# StereoOutputBoard.net
KiCad netlist of a schematic drawn in EAGLE
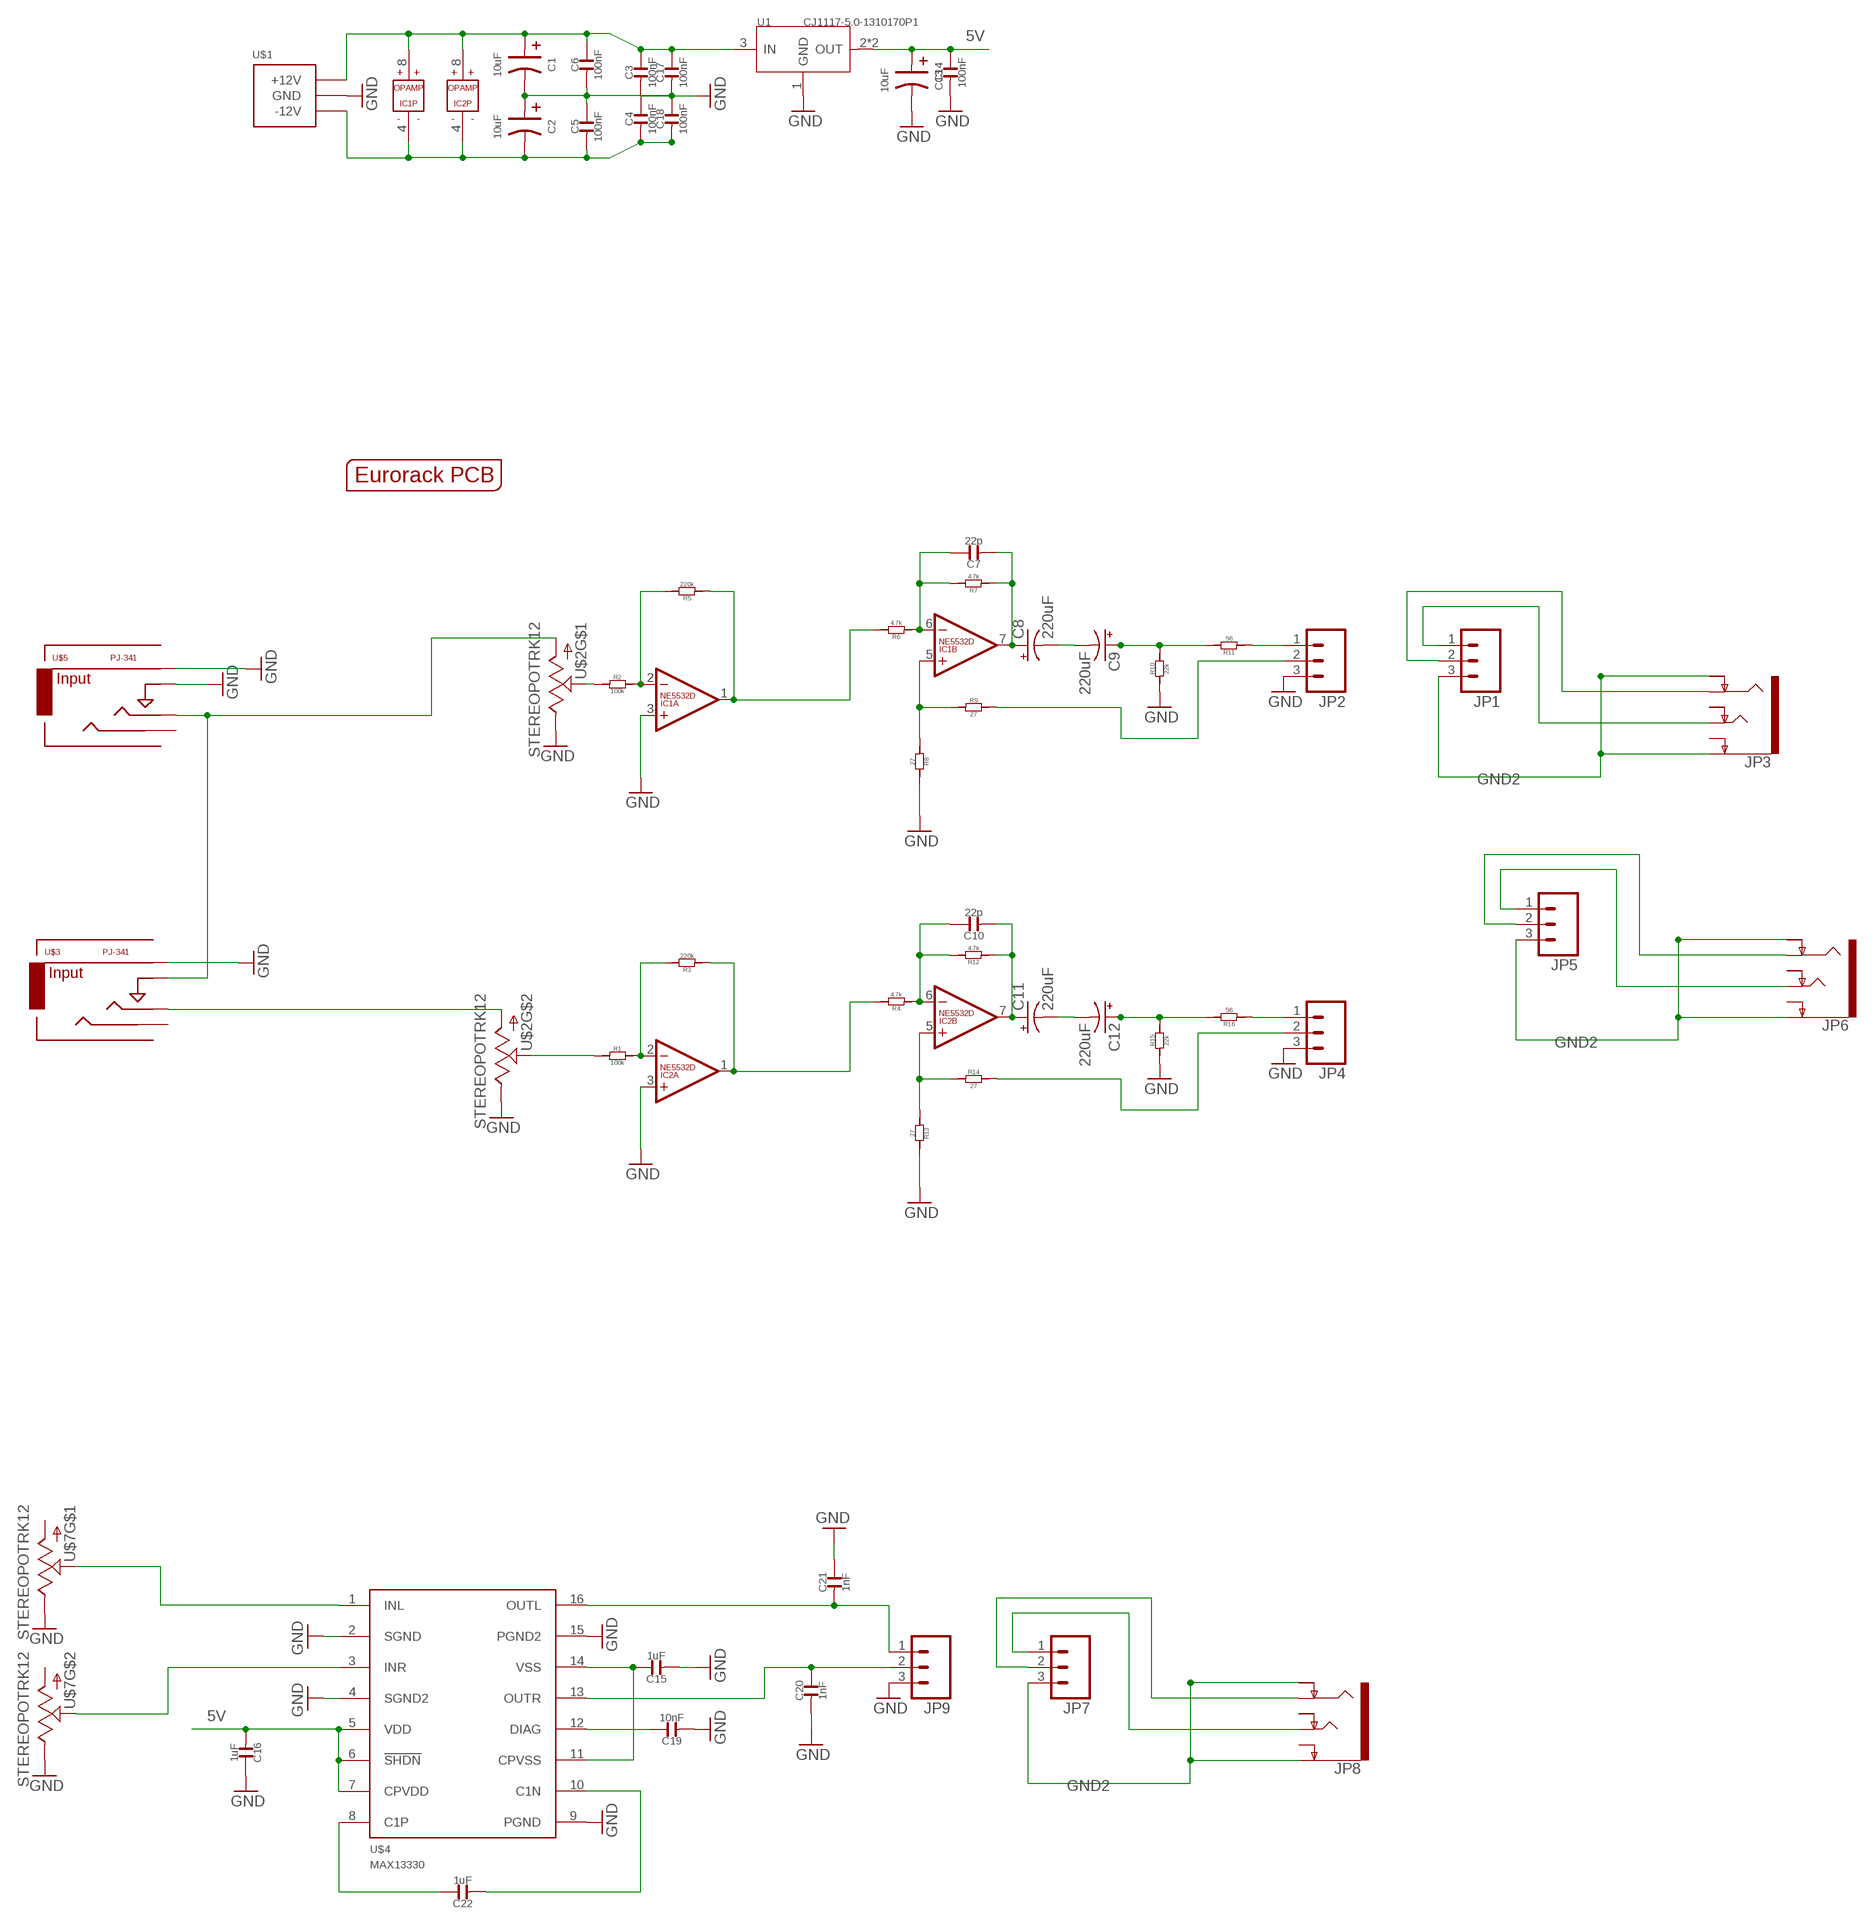
[diagram p0: schematic, sheet 1]

(export (version "E")
  (design (tool "Eeschema 10.0.6"))
  (components
    (comp (ref "C1")
      (value "10uF")
      (footprint "eagle-import:AVX-A")
      (libsource (lib "eagle-import") (part "C-POLAR-A"))
    )
    (comp (ref "C2")
      (value "10uF")
      (footprint "eagle-import:AVX-A")
      (libsource (lib "eagle-import") (part "C-POLAR-A"))
    )
    (comp (ref "C3")
      (value "100nF")
      (footprint "eagle-import:C0603")
      (libsource (lib "eagle-import") (part "C-0603"))
    )
    (comp (ref "C4")
      (value "100nF")
      (footprint "eagle-import:C0603")
      (libsource (lib "eagle-import") (part "C-0603"))
    )
    (comp (ref "C5")
      (value "100nF")
      (footprint "eagle-import:C0603")
      (libsource (lib "eagle-import") (part "C-0603"))
    )
    (comp (ref "C6")
      (value "100nF")
      (footprint "eagle-import:C0603")
      (libsource (lib "eagle-import") (part "C-0603"))
    )
    (comp (ref "C7")
      (value "22p")
      (footprint "eagle-import:C0603")
      (libsource (lib "eagle-import") (part "C-0603"))
    )
    (comp (ref "C8")
      (value "220uF")
      (footprint "eagle-import:153CLV-0505")
      (libsource (lib "eagle-import") (part "CPOL-US153CLV-0505"))
    )
    (comp (ref "C9")
      (value "220uF")
      (footprint "eagle-import:153CLV-0505")
      (libsource (lib "eagle-import") (part "CPOL-US153CLV-0505"))
    )
    (comp (ref "C10")
      (value "22p")
      (footprint "eagle-import:C0603")
      (libsource (lib "eagle-import") (part "C-0603"))
    )
    (comp (ref "C11")
      (value "220uF")
      (footprint "eagle-import:153CLV-0505")
      (libsource (lib "eagle-import") (part "CPOL-US153CLV-0505"))
    )
    (comp (ref "C12")
      (value "220uF")
      (footprint "eagle-import:153CLV-0505")
      (libsource (lib "eagle-import") (part "CPOL-US153CLV-0505"))
    )
    (comp (ref "C13")
      (value "10uF")
      (footprint "eagle-import:AVX-A")
      (libsource (lib "eagle-import") (part "C-POLAR-A"))
    )
    (comp (ref "C14")
      (value "100nF")
      (footprint "eagle-import:C0603")
      (libsource (lib "eagle-import") (part "C-0603"))
    )
    (comp (ref "C15")
      (value "1uF")
      (footprint "eagle-import:C0603")
      (libsource (lib "eagle-import") (part "C-0603"))
    )
    (comp (ref "C16")
      (value "1uF")
      (footprint "eagle-import:C0603")
      (libsource (lib "eagle-import") (part "C-0603"))
    )
    (comp (ref "C17")
      (value "100nF")
      (footprint "eagle-import:C0603")
      (libsource (lib "eagle-import") (part "C-0603"))
    )
    (comp (ref "C18")
      (value "100nF")
      (footprint "eagle-import:C0603")
      (libsource (lib "eagle-import") (part "C-0603"))
    )
    (comp (ref "C19")
      (value "10nF")
      (footprint "eagle-import:C0603")
      (libsource (lib "eagle-import") (part "C-0603"))
    )
    (comp (ref "C20")
      (value "1nF")
      (footprint "eagle-import:C0603")
      (libsource (lib "eagle-import") (part "C-0603"))
    )
    (comp (ref "C21")
      (value "1nF")
      (footprint "eagle-import:C0603")
      (libsource (lib "eagle-import") (part "C-0603"))
    )
    (comp (ref "C22")
      (value "1uF")
      (footprint "eagle-import:C0603")
      (libsource (lib "eagle-import") (part "C-0603"))
    )
    (comp (ref "IC1")
      (value "NE5532D")
      (footprint "eagle-import:SO08")
      (libsource (lib "eagle-import") (part "NE5532D"))
    )
    (comp (ref "IC2")
      (value "NE5532D")
      (footprint "eagle-import:SO08")
      (libsource (lib "eagle-import") (part "NE5532D"))
    )
    (comp (ref "JP1")
      (value "M03PTH")
      (footprint "eagle-import:1X03")
      (libsource (lib "eagle-import") (part "M03PTH"))
    )
    (comp (ref "JP2")
      (value "M03PTH")
      (footprint "eagle-import:1X03")
      (libsource (lib "eagle-import") (part "M03PTH"))
    )
    (comp (ref "JP3")
      (value "AUDIO-JACK4-.25-HORIZ-TRS")
      (footprint "eagle-import:AUDIO-JACK-.25-INCH-HORIZ-PTH")
      (libsource (lib "eagle-import") (part "AUDIO-JACK4-.25-HORIZ-TRS"))
    )
    (comp (ref "JP4")
      (value "M03PTH")
      (footprint "eagle-import:1X03")
      (libsource (lib "eagle-import") (part "M03PTH"))
    )
    (comp (ref "JP5")
      (value "M03PTH")
      (footprint "eagle-import:1X03")
      (libsource (lib "eagle-import") (part "M03PTH"))
    )
    (comp (ref "JP6")
      (value "AUDIO-JACK4-.25-HORIZ-TRS")
      (footprint "eagle-import:AUDIO-JACK-.25-INCH-HORIZ-PTH")
      (libsource (lib "eagle-import") (part "AUDIO-JACK4-.25-HORIZ-TRS"))
    )
    (comp (ref "JP7")
      (value "M03PTH")
      (footprint "eagle-import:1X03")
      (libsource (lib "eagle-import") (part "M03PTH"))
    )
    (comp (ref "JP8")
      (value "AUDIO-JACK4-.25-HORIZ-TRS")
      (footprint "eagle-import:AUDIO-JACK-.25-INCH-HORIZ-PTH")
      (libsource (lib "eagle-import") (part "AUDIO-JACK4-.25-HORIZ-TRS"))
    )
    (comp (ref "JP9")
      (value "M03PTH")
      (footprint "eagle-import:1X03")
      (libsource (lib "eagle-import") (part "M03PTH"))
    )
    (comp (ref "R1")
      (value "100k")
      (footprint "eagle-import:R0603")
      (libsource (lib "eagle-import") (part "R-0603"))
    )
    (comp (ref "R2")
      (value "100k")
      (footprint "eagle-import:R0603")
      (libsource (lib "eagle-import") (part "R-0603"))
    )
    (comp (ref "R3")
      (value "220k")
      (footprint "eagle-import:R0603")
      (libsource (lib "eagle-import") (part "R-0603"))
    )
    (comp (ref "R4")
      (value "4.7k")
      (footprint "eagle-import:R0603")
      (libsource (lib "eagle-import") (part "R-0603"))
    )
    (comp (ref "R5")
      (value "220k")
      (footprint "eagle-import:R0603")
      (libsource (lib "eagle-import") (part "R-0603"))
    )
    (comp (ref "R6")
      (value "4.7k")
      (footprint "eagle-import:R0603")
      (libsource (lib "eagle-import") (part "R-0603"))
    )
    (comp (ref "R7")
      (value "4.7k")
      (footprint "eagle-import:R0603")
      (libsource (lib "eagle-import") (part "R-0603"))
    )
    (comp (ref "R8")
      (value "27")
      (footprint "eagle-import:R0603")
      (libsource (lib "eagle-import") (part "R-0603"))
    )
    (comp (ref "R9")
      (value "27")
      (footprint "eagle-import:R0603")
      (libsource (lib "eagle-import") (part "R-0603"))
    )
    (comp (ref "R10")
      (value "22k")
      (footprint "eagle-import:R0603")
      (libsource (lib "eagle-import") (part "R-0603"))
    )
    (comp (ref "R11")
      (value "56")
      (footprint "eagle-import:R0603")
      (libsource (lib "eagle-import") (part "R-0603"))
    )
    (comp (ref "R12")
      (value "4.7k")
      (footprint "eagle-import:R0603")
      (libsource (lib "eagle-import") (part "R-0603"))
    )
    (comp (ref "R13")
      (value "27")
      (footprint "eagle-import:R0603")
      (libsource (lib "eagle-import") (part "R-0603"))
    )
    (comp (ref "R14")
      (value "27")
      (footprint "eagle-import:R0603")
      (libsource (lib "eagle-import") (part "R-0603"))
    )
    (comp (ref "R15")
      (value "22k")
      (footprint "eagle-import:R0603")
      (libsource (lib "eagle-import") (part "R-0603"))
    )
    (comp (ref "R16")
      (value "56")
      (footprint "eagle-import:R0603")
      (libsource (lib "eagle-import") (part "R-0603"))
    )
    (comp (ref "U$1")
      (value "POWER_SIMPLE")
      (footprint "eagle-import:2X05_SMT_HEADER")
      (libsource (lib "eagle-import") (part "POWER_SIMPLE"))
    )
    (comp (ref "U$2")
      (value "STEREOPOTRK12")
      (footprint "eagle-import:RK12")
      (libsource (lib "eagle-import") (part "STEREOPOTRK12"))
    )
    (comp (ref "U$3")
      (value "PJ-341")
      (footprint "eagle-import:3.5MM-JACK-SWITCH-13MM-INPUT")
      (libsource (lib "eagle-import") (part "AUDIO-JACKINPUT"))
    )
    (comp (ref "U$4")
      (value "MAX13330")
      (footprint "eagle-import:QSOP16")
      (libsource (lib "eagle-import") (part "MAX13330"))
    )
    (comp (ref "U$5")
      (value "PJ-341")
      (footprint "eagle-import:3.5MM-JACK-SWITCH-13MM-INPUT")
      (libsource (lib "eagle-import") (part "AUDIO-JACKINPUT"))
    )
    (comp (ref "U$6")
      (value "EURORACK_PCB4HP")
      (footprint "eagle-import:EURORACK4HPPCB")
      (libsource (lib "eagle-import") (part "EURORACK_PCB4HP"))
    )
    (comp (ref "U$7")
      (value "STEREOPOTRK12")
      (footprint "eagle-import:RK12")
      (libsource (lib "eagle-import") (part "STEREOPOTRK12"))
    )
    (comp (ref "U1")
      (value "CJ1117-5.0-1310170P1")
      (footprint "eagle-import:SOT223")
      (libsource (lib "eagle-import") (part "CJ1117-5.0-1310170P1"))
    )
  )
  (nets
    (net (code "1") (name "/5V") (class "Default")
      (node (ref "C13") (pin "+") (pinfunction "1_+") (pintype "bidirectional"))
      (node (ref "C14") (pin "2") (pinfunction "2_2") (pintype "bidirectional"))
      (node (ref "C16") (pin "1") (pinfunction "1_1") (pintype "bidirectional"))
      (node (ref "U$4") (pin "5") (pinfunction "VDD_5") (pintype "bidirectional"))
      (node (ref "U$4") (pin "6") (pinfunction "~{SHDN}_6") (pintype "bidirectional"))
      (node (ref "U$4") (pin "7") (pinfunction "CPVDD_7") (pintype "bidirectional"))
      (node (ref "U1") (pin "2") (pinfunction "OUT_2") (pintype "bidirectional"))
      (node (ref "U1") (pin "TER") (pinfunction "OUT_TER") (pintype "bidirectional"))
    )
    (net (code "2") (name "/GND2") (class "Default")
      (node (ref "JP1") (pin "3") (pinfunction "3_3") (pintype "passive"))
      (node (ref "JP3") (pin "P$2") (pinfunction "EARTH_P$2") (pintype "bidirectional"))
      (node (ref "JP3") (pin "P$5") (pinfunction "RING-NORM_P$5") (pintype "bidirectional"))
      (node (ref "JP5") (pin "3") (pinfunction "3_3") (pintype "passive"))
      (node (ref "JP6") (pin "P$2") (pinfunction "EARTH_P$2") (pintype "bidirectional"))
      (node (ref "JP6") (pin "P$5") (pinfunction "RING-NORM_P$5") (pintype "bidirectional"))
      (node (ref "JP7") (pin "3") (pinfunction "3_3") (pintype "passive"))
      (node (ref "JP8") (pin "P$2") (pinfunction "EARTH_P$2") (pintype "bidirectional"))
      (node (ref "JP8") (pin "P$5") (pinfunction "RING-NORM_P$5") (pintype "bidirectional"))
    )
    (net (code "3") (name "GND") (class "Default")
      (node (ref "C1") (pin "-") (pinfunction "2_-") (pintype "bidirectional"))
      (node (ref "C13") (pin "-") (pinfunction "2_-") (pintype "bidirectional"))
      (node (ref "C14") (pin "1") (pinfunction "1_1") (pintype "bidirectional"))
      (node (ref "C15") (pin "1") (pinfunction "1_1") (pintype "bidirectional"))
      (node (ref "C16") (pin "2") (pinfunction "2_2") (pintype "bidirectional"))
      (node (ref "C17") (pin "1") (pinfunction "1_1") (pintype "bidirectional"))
      (node (ref "C18") (pin "2") (pinfunction "2_2") (pintype "bidirectional"))
      (node (ref "C19") (pin "1") (pinfunction "1_1") (pintype "bidirectional"))
      (node (ref "C2") (pin "+") (pinfunction "1_+") (pintype "bidirectional"))
      (node (ref "C20") (pin "1") (pinfunction "1_1") (pintype "bidirectional"))
      (node (ref "C21") (pin "2") (pinfunction "2_2") (pintype "bidirectional"))
      (node (ref "C3") (pin "1") (pinfunction "1_1") (pintype "bidirectional"))
      (node (ref "C4") (pin "2") (pinfunction "2_2") (pintype "bidirectional"))
      (node (ref "C5") (pin "2") (pinfunction "2_2") (pintype "bidirectional"))
      (node (ref "C6") (pin "1") (pinfunction "1_1") (pintype "bidirectional"))
      (node (ref "IC1") (pin "3") (pinfunction "+IN_3") (pintype "input"))
      (node (ref "IC2") (pin "3") (pinfunction "+IN_3") (pintype "input"))
      (node (ref "JP2") (pin "3") (pinfunction "3_3") (pintype "passive"))
      (node (ref "JP4") (pin "3") (pinfunction "3_3") (pintype "passive"))
      (node (ref "JP9") (pin "3") (pinfunction "3_3") (pintype "passive"))
      (node (ref "R10") (pin "1") (pinfunction "1_1") (pintype "bidirectional"))
      (node (ref "R13") (pin "2") (pinfunction "2_2") (pintype "bidirectional"))
      (node (ref "R15") (pin "1") (pinfunction "1_1") (pintype "bidirectional"))
      (node (ref "R8") (pin "2") (pinfunction "2_2") (pintype "bidirectional"))
      (node (ref "U$1") (pin "3") (pinfunction "GND_3") (pintype "bidirectional"))
      (node (ref "U$1") (pin "4") (pinfunction "GND_4") (pintype "bidirectional"))
      (node (ref "U$1") (pin "5") (pinfunction "GND_5") (pintype "bidirectional"))
      (node (ref "U$1") (pin "6") (pinfunction "GND_6") (pintype "bidirectional"))
      (node (ref "U$1") (pin "7") (pinfunction "GND_7") (pintype "bidirectional"))
      (node (ref "U$1") (pin "8") (pinfunction "GND_8") (pintype "bidirectional"))
      (node (ref "U$2") (pin "R1_1") (pinfunction "E_R1_1") (pintype "passive"))
      (node (ref "U$2") (pin "R2_1") (pinfunction "E_R2_1") (pintype "passive"))
      (node (ref "U$3") (pin "RING@3") (pinfunction "RING_RING@3") (pintype "bidirectional"))
      (node (ref "U$4") (pin "15") (pinfunction "PGND2_15") (pintype "bidirectional"))
      (node (ref "U$4") (pin "2") (pinfunction "SGND_2") (pintype "bidirectional"))
      (node (ref "U$4") (pin "4") (pinfunction "SGND2_4") (pintype "bidirectional"))
      (node (ref "U$4") (pin "9") (pinfunction "PGND_9") (pintype "bidirectional"))
      (node (ref "U$5") (pin "RING@3") (pinfunction "RING_RING@3") (pintype "bidirectional"))
      (node (ref "U$5") (pin "SWITCH@3") (pinfunction "SWITCH_SWITCH@3") (pintype "bidirectional"))
      (node (ref "U$7") (pin "R1_1") (pinfunction "E_R1_1") (pintype "passive"))
      (node (ref "U$7") (pin "R2_1") (pinfunction "E_R2_1") (pintype "passive"))
      (node (ref "U1") (pin "1") (pinfunction "GND_1") (pintype "bidirectional"))
    )
    (net (code "4") (name "Net-(C1-1)") (class "Default")
      (node (ref "C1") (pin "+") (pinfunction "1_+") (pintype "bidirectional"))
      (node (ref "C17") (pin "2") (pinfunction "2_2") (pintype "bidirectional"))
      (node (ref "C3") (pin "2") (pinfunction "2_2") (pintype "bidirectional"))
      (node (ref "C6") (pin "2") (pinfunction "2_2") (pintype "bidirectional"))
      (node (ref "IC1") (pin "8") (pinfunction "V+_8") (pintype "power_in"))
      (node (ref "IC2") (pin "8") (pinfunction "V+_8") (pintype "power_in"))
      (node (ref "U$1") (pin "10") (pinfunction "+12V_10") (pintype "bidirectional"))
      (node (ref "U$1") (pin "9") (pinfunction "+12V_9") (pintype "bidirectional"))
      (node (ref "U1") (pin "3") (pinfunction "IN_3") (pintype "bidirectional"))
    )
    (net (code "5") (name "Net-(C2-2)") (class "Default")
      (node (ref "C18") (pin "1") (pinfunction "1_1") (pintype "bidirectional"))
      (node (ref "C2") (pin "-") (pinfunction "2_-") (pintype "bidirectional"))
      (node (ref "C4") (pin "1") (pinfunction "1_1") (pintype "bidirectional"))
      (node (ref "C5") (pin "1") (pinfunction "1_1") (pintype "bidirectional"))
      (node (ref "IC1") (pin "4") (pinfunction "V-_4") (pintype "power_in"))
      (node (ref "IC2") (pin "4") (pinfunction "V-_4") (pintype "power_in"))
      (node (ref "U$1") (pin "1") (pinfunction "-12V_1") (pintype "bidirectional"))
      (node (ref "U$1") (pin "2") (pinfunction "-12V_2") (pintype "bidirectional"))
    )
    (net (code "6") (name "Net-(C8-Pad-)") (class "Default")
      (node (ref "C8") (pin "-") (pinfunction "-_-") (pintype "passive"))
      (node (ref "C9") (pin "-") (pinfunction "-_-") (pintype "passive"))
    )
    (net (code "7") (name "Net-(C9-Pad+)") (class "Default")
      (node (ref "C9") (pin "+") (pinfunction "+_+") (pintype "passive"))
      (node (ref "R10") (pin "2") (pinfunction "2_2") (pintype "bidirectional"))
      (node (ref "R11") (pin "2") (pinfunction "2_2") (pintype "bidirectional"))
    )
    (net (code "8") (name "Net-(C11-Pad-)") (class "Default")
      (node (ref "C11") (pin "-") (pinfunction "-_-") (pintype "passive"))
      (node (ref "C12") (pin "-") (pinfunction "-_-") (pintype "passive"))
    )
    (net (code "9") (name "Net-(C12-Pad+)") (class "Default")
      (node (ref "C12") (pin "+") (pinfunction "+_+") (pintype "passive"))
      (node (ref "R15") (pin "2") (pinfunction "2_2") (pintype "bidirectional"))
      (node (ref "R16") (pin "2") (pinfunction "2_2") (pintype "bidirectional"))
    )
    (net (code "10") (name "Net-(IC1A--IN)") (class "Default")
      (node (ref "IC1") (pin "2") (pinfunction "-IN_2") (pintype "input"))
      (node (ref "R2") (pin "2") (pinfunction "2_2") (pintype "bidirectional"))
      (node (ref "R5") (pin "2") (pinfunction "2_2") (pintype "bidirectional"))
    )
    (net (code "11") (name "Net-(IC1A-OUT)") (class "Default")
      (node (ref "IC1") (pin "1") (pinfunction "OUT_1") (pintype "output"))
      (node (ref "R5") (pin "1") (pinfunction "1_1") (pintype "bidirectional"))
      (node (ref "R6") (pin "2") (pinfunction "2_2") (pintype "bidirectional"))
    )
    (net (code "12") (name "Net-(IC1B-+IN)") (class "Default")
      (node (ref "IC1") (pin "5") (pinfunction "+IN_5") (pintype "input"))
      (node (ref "R8") (pin "1") (pinfunction "1_1") (pintype "bidirectional"))
      (node (ref "R9") (pin "1") (pinfunction "1_1") (pintype "bidirectional"))
    )
    (net (code "13") (name "Net-(IC1B--IN)") (class "Default")
      (node (ref "C7") (pin "2") (pinfunction "2_2") (pintype "bidirectional"))
      (node (ref "IC1") (pin "6") (pinfunction "-IN_6") (pintype "input"))
      (node (ref "R6") (pin "1") (pinfunction "1_1") (pintype "bidirectional"))
      (node (ref "R7") (pin "2") (pinfunction "2_2") (pintype "bidirectional"))
    )
    (net (code "14") (name "Net-(IC1B-OUT)") (class "Default")
      (node (ref "C7") (pin "1") (pinfunction "1_1") (pintype "bidirectional"))
      (node (ref "C8") (pin "+") (pinfunction "+_+") (pintype "passive"))
      (node (ref "IC1") (pin "7") (pinfunction "OUT_7") (pintype "output"))
      (node (ref "R7") (pin "1") (pinfunction "1_1") (pintype "bidirectional"))
    )
    (net (code "15") (name "Net-(IC2A--IN)") (class "Default")
      (node (ref "IC2") (pin "2") (pinfunction "-IN_2") (pintype "input"))
      (node (ref "R1") (pin "2") (pinfunction "2_2") (pintype "bidirectional"))
      (node (ref "R3") (pin "2") (pinfunction "2_2") (pintype "bidirectional"))
    )
    (net (code "16") (name "Net-(IC2A-OUT)") (class "Default")
      (node (ref "IC2") (pin "1") (pinfunction "OUT_1") (pintype "output"))
      (node (ref "R3") (pin "1") (pinfunction "1_1") (pintype "bidirectional"))
      (node (ref "R4") (pin "2") (pinfunction "2_2") (pintype "bidirectional"))
    )
    (net (code "17") (name "Net-(IC2B-+IN)") (class "Default")
      (node (ref "IC2") (pin "5") (pinfunction "+IN_5") (pintype "input"))
      (node (ref "R13") (pin "1") (pinfunction "1_1") (pintype "bidirectional"))
      (node (ref "R14") (pin "1") (pinfunction "1_1") (pintype "bidirectional"))
    )
    (net (code "18") (name "Net-(IC2B--IN)") (class "Default")
      (node (ref "C10") (pin "2") (pinfunction "2_2") (pintype "bidirectional"))
      (node (ref "IC2") (pin "6") (pinfunction "-IN_6") (pintype "input"))
      (node (ref "R12") (pin "2") (pinfunction "2_2") (pintype "bidirectional"))
      (node (ref "R4") (pin "1") (pinfunction "1_1") (pintype "bidirectional"))
    )
    (net (code "19") (name "Net-(IC2B-OUT)") (class "Default")
      (node (ref "C10") (pin "1") (pinfunction "1_1") (pintype "bidirectional"))
      (node (ref "C11") (pin "+") (pinfunction "+_+") (pintype "passive"))
      (node (ref "IC2") (pin "7") (pinfunction "OUT_7") (pintype "output"))
      (node (ref "R12") (pin "1") (pinfunction "1_1") (pintype "bidirectional"))
    )
    (net (code "20") (name "Net-(JP2-Pad1)") (class "Default")
      (node (ref "JP2") (pin "1") (pinfunction "1_1") (pintype "passive"))
      (node (ref "R11") (pin "1") (pinfunction "1_1") (pintype "bidirectional"))
    )
    (net (code "21") (name "Net-(JP2-Pad2)") (class "Default")
      (node (ref "JP2") (pin "2") (pinfunction "2_2") (pintype "passive"))
      (node (ref "R9") (pin "2") (pinfunction "2_2") (pintype "bidirectional"))
    )
    (net (code "22") (name "Net-(JP3-RING)") (class "Default")
      (node (ref "JP1") (pin "2") (pinfunction "2_2") (pintype "passive"))
      (node (ref "JP3") (pin "P$4") (pinfunction "RING_P$4") (pintype "bidirectional"))
    )
    (net (code "23") (name "Net-(JP3-TIP)") (class "Default")
      (node (ref "JP1") (pin "1") (pinfunction "1_1") (pintype "passive"))
      (node (ref "JP3") (pin "P$6") (pinfunction "TIP_P$6") (pintype "bidirectional"))
    )
    (net (code "24") (name "Net-(JP4-Pad1)") (class "Default")
      (node (ref "JP4") (pin "1") (pinfunction "1_1") (pintype "passive"))
      (node (ref "R16") (pin "1") (pinfunction "1_1") (pintype "bidirectional"))
    )
    (net (code "25") (name "Net-(JP4-Pad2)") (class "Default")
      (node (ref "JP4") (pin "2") (pinfunction "2_2") (pintype "passive"))
      (node (ref "R14") (pin "2") (pinfunction "2_2") (pintype "bidirectional"))
    )
    (net (code "26") (name "Net-(JP6-RING)") (class "Default")
      (node (ref "JP5") (pin "2") (pinfunction "2_2") (pintype "passive"))
      (node (ref "JP6") (pin "P$4") (pinfunction "RING_P$4") (pintype "bidirectional"))
    )
    (net (code "27") (name "Net-(JP6-TIP)") (class "Default")
      (node (ref "JP5") (pin "1") (pinfunction "1_1") (pintype "passive"))
      (node (ref "JP6") (pin "P$6") (pinfunction "TIP_P$6") (pintype "bidirectional"))
    )
    (net (code "28") (name "Net-(JP8-RING)") (class "Default")
      (node (ref "JP7") (pin "2") (pinfunction "2_2") (pintype "passive"))
      (node (ref "JP8") (pin "P$4") (pinfunction "RING_P$4") (pintype "bidirectional"))
    )
    (net (code "29") (name "Net-(JP8-TIP)") (class "Default")
      (node (ref "JP7") (pin "1") (pinfunction "1_1") (pintype "passive"))
      (node (ref "JP8") (pin "P$6") (pinfunction "TIP_P$6") (pintype "bidirectional"))
    )
    (net (code "30") (name "Net-(U$2A-A)") (class "Default")
      (node (ref "U$2") (pin "R1_3") (pinfunction "A_R1_3") (pintype "passive"))
      (node (ref "U$3") (pin "SWITCH@3") (pinfunction "SWITCH_SWITCH@3") (pintype "bidirectional"))
      (node (ref "U$5") (pin "TIP@3") (pinfunction "TIP_TIP@3") (pintype "bidirectional"))
    )
    (net (code "31") (name "Net-(U$2A-S)") (class "Default")
      (node (ref "R2") (pin "1") (pinfunction "1_1") (pintype "bidirectional"))
      (node (ref "U$2") (pin "R1_2") (pinfunction "S_R1_2") (pintype "passive"))
    )
    (net (code "32") (name "Net-(U$2B-A)") (class "Default")
      (node (ref "U$2") (pin "R2_3") (pinfunction "A_R2_3") (pintype "passive"))
      (node (ref "U$3") (pin "TIP@3") (pinfunction "TIP_TIP@3") (pintype "bidirectional"))
    )
    (net (code "33") (name "Net-(U$2B-S)") (class "Default")
      (node (ref "R1") (pin "1") (pinfunction "1_1") (pintype "bidirectional"))
      (node (ref "U$2") (pin "R2_2") (pinfunction "S_R2_2") (pintype "passive"))
    )
    (net (code "34") (name "Net-(U$4-C1N)") (class "Default")
      (node (ref "C22") (pin "1") (pinfunction "1_1") (pintype "bidirectional"))
      (node (ref "U$4") (pin "10") (pinfunction "C1N_10") (pintype "bidirectional"))
    )
    (net (code "35") (name "Net-(U$4-C1P)") (class "Default")
      (node (ref "C22") (pin "2") (pinfunction "2_2") (pintype "bidirectional"))
      (node (ref "U$4") (pin "8") (pinfunction "C1P_8") (pintype "bidirectional"))
    )
    (net (code "36") (name "Net-(U$4-CPVSS)") (class "Default")
      (node (ref "C15") (pin "2") (pinfunction "2_2") (pintype "bidirectional"))
      (node (ref "U$4") (pin "11") (pinfunction "CPVSS_11") (pintype "bidirectional"))
      (node (ref "U$4") (pin "14") (pinfunction "VSS_14") (pintype "bidirectional"))
    )
    (net (code "37") (name "Net-(U$4-DIAG)") (class "Default")
      (node (ref "C19") (pin "2") (pinfunction "2_2") (pintype "bidirectional"))
      (node (ref "U$4") (pin "12") (pinfunction "DIAG_12") (pintype "bidirectional"))
    )
    (net (code "38") (name "Net-(U$4-INL)") (class "Default")
      (node (ref "U$4") (pin "1") (pinfunction "INL_1") (pintype "bidirectional"))
      (node (ref "U$7") (pin "R1_2") (pinfunction "S_R1_2") (pintype "passive"))
    )
    (net (code "39") (name "Net-(U$4-INR)") (class "Default")
      (node (ref "U$4") (pin "3") (pinfunction "INR_3") (pintype "bidirectional"))
      (node (ref "U$7") (pin "R2_2") (pinfunction "S_R2_2") (pintype "passive"))
    )
    (net (code "40") (name "Net-(U$4-OUTL)") (class "Default")
      (node (ref "C21") (pin "1") (pinfunction "1_1") (pintype "bidirectional"))
      (node (ref "JP9") (pin "1") (pinfunction "1_1") (pintype "passive"))
      (node (ref "U$4") (pin "16") (pinfunction "OUTL_16") (pintype "bidirectional"))
    )
    (net (code "41") (name "Net-(U$4-OUTR)") (class "Default")
      (node (ref "C20") (pin "2") (pinfunction "2_2") (pintype "bidirectional"))
      (node (ref "JP9") (pin "2") (pinfunction "2_2") (pintype "passive"))
      (node (ref "U$4") (pin "13") (pinfunction "OUTR_13") (pintype "bidirectional"))
    )
    (net (code "42") (name "unconnected-(JP3-EARTH-NORM-PadP$3)") (class "Default")
      (node (ref "JP3") (pin "P$3") (pinfunction "EARTH-NORM_P$3") (pintype "bidirectional"))
    )
    (net (code "43") (name "unconnected-(JP3-TIP-NORM-PadP$7)") (class "Default")
      (node (ref "JP3") (pin "P$7") (pinfunction "TIP-NORM_P$7") (pintype "bidirectional"))
    )
    (net (code "44") (name "unconnected-(JP6-EARTH-NORM-PadP$3)") (class "Default")
      (node (ref "JP6") (pin "P$3") (pinfunction "EARTH-NORM_P$3") (pintype "bidirectional"))
    )
    (net (code "45") (name "unconnected-(JP6-TIP-NORM-PadP$7)") (class "Default")
      (node (ref "JP6") (pin "P$7") (pinfunction "TIP-NORM_P$7") (pintype "bidirectional"))
    )
    (net (code "46") (name "unconnected-(JP8-EARTH-NORM-PadP$3)") (class "Default")
      (node (ref "JP8") (pin "P$3") (pinfunction "EARTH-NORM_P$3") (pintype "bidirectional"))
    )
    (net (code "47") (name "unconnected-(JP8-TIP-NORM-PadP$7)") (class "Default")
      (node (ref "JP8") (pin "P$7") (pinfunction "TIP-NORM_P$7") (pintype "bidirectional"))
    )
    (net (code "48") (name "unconnected-(U$3-SECOND-PadSECOND@3)") (class "Default")
      (node (ref "U$3") (pin "SECOND@3") (pinfunction "SECOND_SECOND@3") (pintype "bidirectional"))
    )
    (net (code "49") (name "unconnected-(U$5-SECOND-PadSECOND@3)") (class "Default")
      (node (ref "U$5") (pin "SECOND@3") (pinfunction "SECOND_SECOND@3") (pintype "bidirectional"))
    )
    (net (code "50") (name "unconnected-(U$7A-A-PadR1_3)") (class "Default")
      (node (ref "U$7") (pin "R1_3") (pinfunction "A_R1_3") (pintype "passive"))
    )
    (net (code "51") (name "unconnected-(U$7B-A-PadR2_3)") (class "Default")
      (node (ref "U$7") (pin "R2_3") (pinfunction "A_R2_3") (pintype "passive"))
    )
  )
)
